# SparkFun_Roshamglo.net
KiCad netlist of a schematic drawn in EAGLE
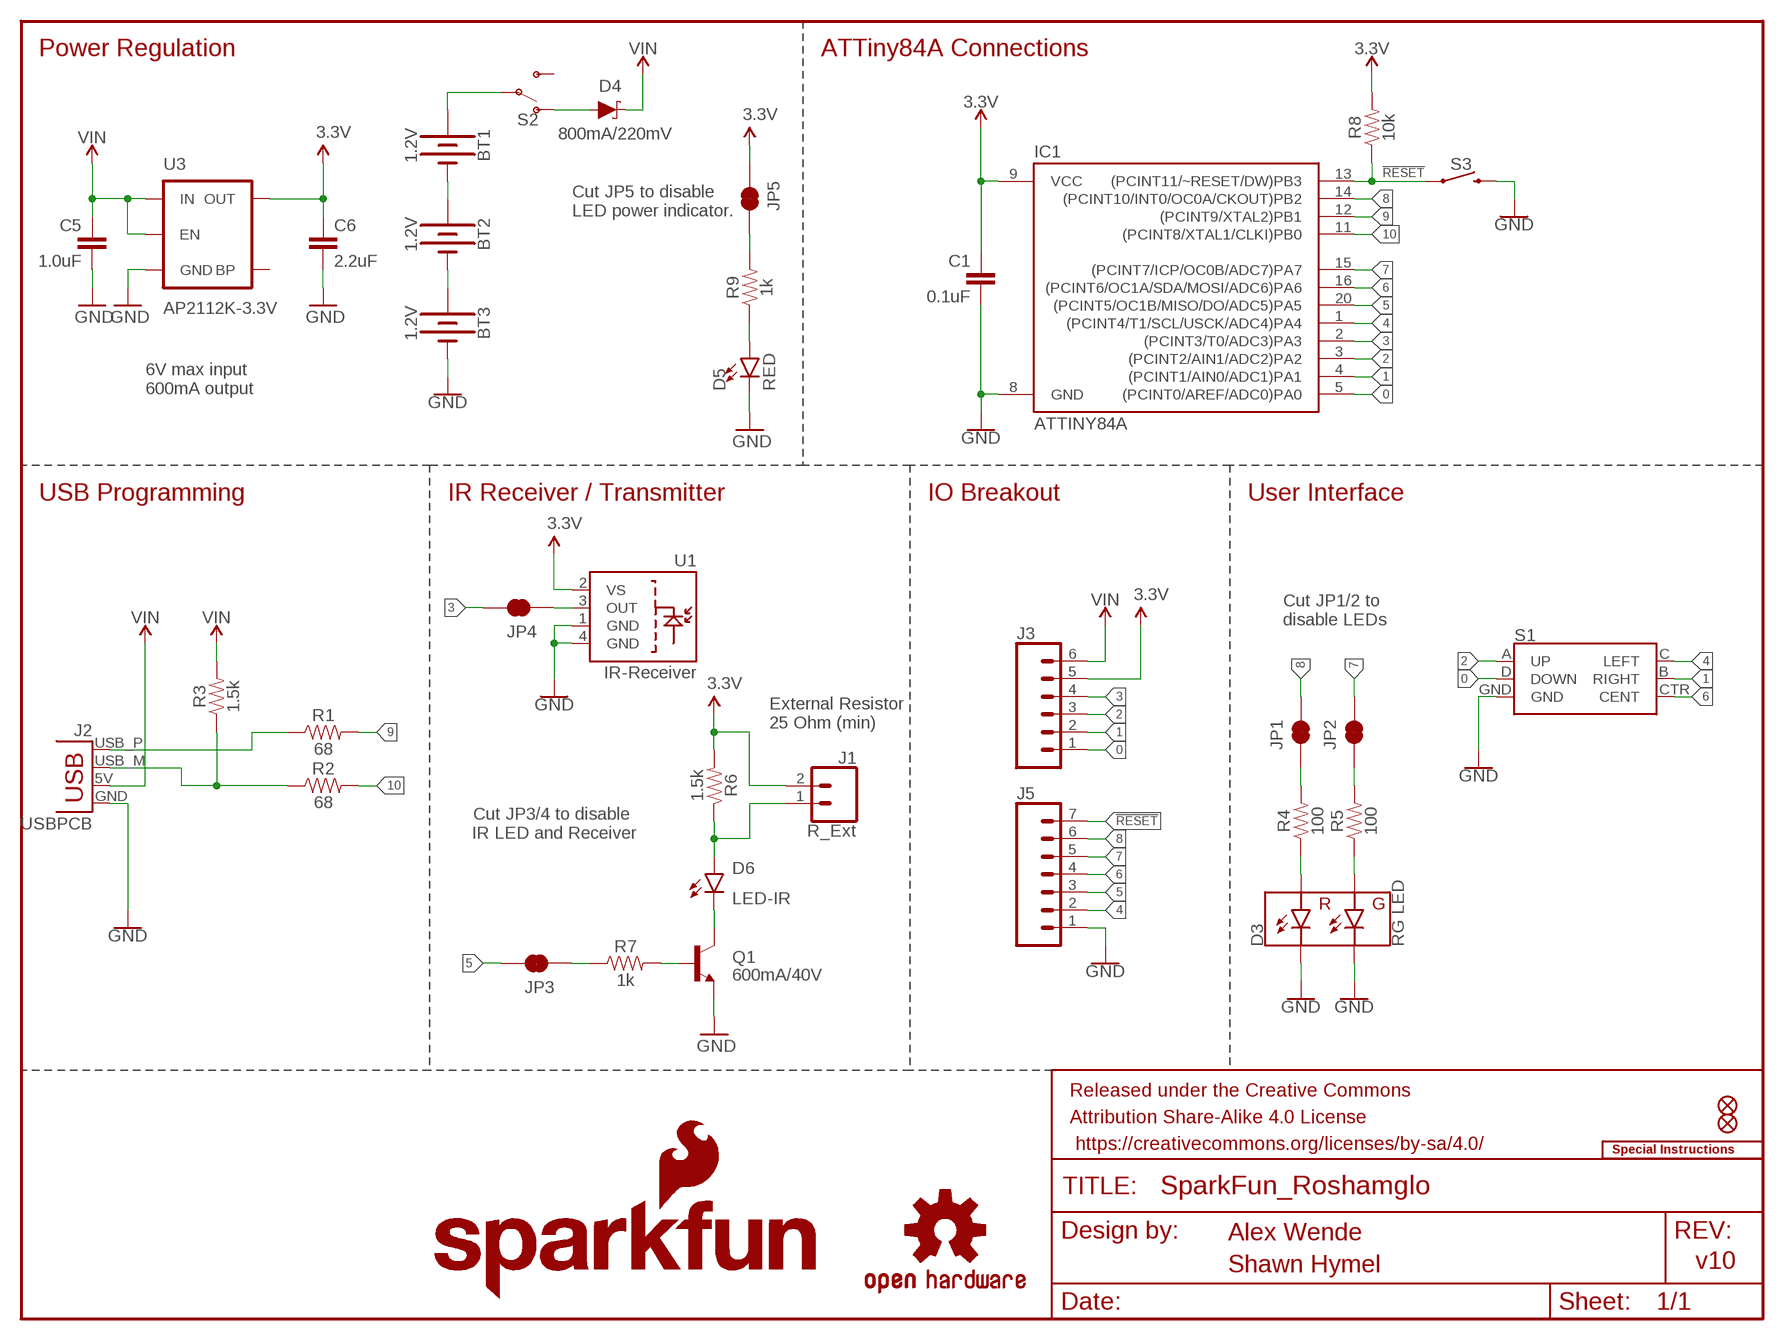
[diagram p0: schematic, sheet 1]

(export (version "E")
  (design (tool "Eeschema 10.0.6"))
  (components
    (comp (ref "BT1")
      (value "1.2V")
      (footprint "eagle-import:BATTERY-AAA-KIT")
      (libsource (lib "eagle-import") (part "BATTERY-AAA_KIT"))
    )
    (comp (ref "BT2")
      (value "1.2V")
      (footprint "eagle-import:BATTERY-AAA-KIT")
      (libsource (lib "eagle-import") (part "BATTERY-AAA_KIT"))
    )
    (comp (ref "BT3")
      (value "1.2V")
      (footprint "eagle-import:BATTERY-AAA-KIT")
      (libsource (lib "eagle-import") (part "BATTERY-AAA_KIT"))
    )
    (comp (ref "C1")
      (value "0.1uF")
      (footprint "eagle-import:0603")
      (libsource (lib "eagle-import") (part "0.1UF-0603-25V-(+80/-20%)"))
    )
    (comp (ref "C5")
      (value "1.0uF")
      (footprint "eagle-import:0805-CAP")
      (libsource (lib "eagle-import") (part "1.0UF-25V-+80/-20(0805){dblquote}"))
    )
    (comp (ref "C6")
      (value "2.2uF")
      (footprint "eagle-import:0603-CAP")
      (libsource (lib "eagle-import") (part "2.2UF-10V-20%(0603)"))
    )
    (comp (ref "D3")
      (value "RG LED")
      (footprint "eagle-import:LTST-C195KGJRKT")
      (libsource (lib "eagle-import") (part "LED-RGLTST-C195KGJRKT"))
    )
    (comp (ref "D4")
      (value "800mA/220mV")
      (footprint "eagle-import:SOD-323")
      (libsource (lib "eagle-import") (part "CUS08F30SOD-323"))
    )
    (comp (ref "D5")
      (value "RED")
      (footprint "eagle-import:LED-0603")
      (libsource (lib "eagle-import") (part "LED-RED0603"))
    )
    (comp (ref "D6")
      (value "LED-IR")
      (footprint "eagle-import:SFH4045N")
      (libsource (lib "eagle-import") (part "LED-IR-SMDSFH4045N"))
    )
    (comp (ref "FD1")
      (value "FIDUCIALUFIDUCIAL")
      (footprint "eagle-import:FIDUCIAL-MICRO")
      (libsource (lib "eagle-import") (part "FIDUCIALUFIDUCIAL"))
    )
    (comp (ref "FD2")
      (value "FIDUCIALUFIDUCIAL")
      (footprint "eagle-import:FIDUCIAL-MICRO")
      (libsource (lib "eagle-import") (part "FIDUCIALUFIDUCIAL"))
    )
    (comp (ref "FRAME1")
      (value "FRAME-LETTER")
      (footprint "eagle-import:CREATIVE_COMMONS")
      (libsource (lib "eagle-import") (part "FRAME-LETTER"))
    )
    (comp (ref "IC1")
      (value "ATTINY84A")
      (footprint "eagle-import:QFN20")
      (libsource (lib "eagle-import") (part "ATTINY84ATTINY84-20MU"))
    )
    (comp (ref "J1")
      (value "R_Ext")
      (footprint "eagle-import:1X02_NO_SILK")
      (libsource (lib "eagle-import") (part "CONN_021X02_NO_SILK"))
    )
    (comp (ref "J2")
      (value "USBPCB")
      (footprint "eagle-import:USB-A-PCB-NOPASTE")
      (libsource (lib "eagle-import") (part "USBPCB_NOPASTE"))
    )
    (comp (ref "J3")
      (value "CONN_06NO_SILK_FEMALE_PTH")
      (footprint "eagle-import:1X06_NO_SILK")
      (libsource (lib "eagle-import") (part "CONN_06NO_SILK_FEMALE_PTH"))
    )
    (comp (ref "J5")
      (value "CONN_07NO_SILK")
      (footprint "eagle-import:1X07_NO_SILK")
      (libsource (lib "eagle-import") (part "CONN_07NO_SILK"))
    )
    (comp (ref "JP1")
      (value "JUMPER-SMT_2_NC_TRACE_SILK")
      (footprint "eagle-import:SMT-JUMPER_2_NC_TRACE_SILK")
      (libsource (lib "eagle-import") (part "JUMPER-SMT_2_NC_TRACE_SILK"))
    )
    (comp (ref "JP2")
      (value "JUMPER-SMT_2_NC_TRACE_SILK")
      (footprint "eagle-import:SMT-JUMPER_2_NC_TRACE_SILK")
      (libsource (lib "eagle-import") (part "JUMPER-SMT_2_NC_TRACE_SILK"))
    )
    (comp (ref "JP3")
      (value "JUMPER-SMT_2_NC_TRACE_SILK")
      (footprint "eagle-import:SMT-JUMPER_2_NC_TRACE_SILK")
      (libsource (lib "eagle-import") (part "JUMPER-SMT_2_NC_TRACE_SILK"))
    )
    (comp (ref "JP4")
      (value "JUMPER-SMT_2_NC_TRACE_SILK")
      (footprint "eagle-import:SMT-JUMPER_2_NC_TRACE_SILK")
      (libsource (lib "eagle-import") (part "JUMPER-SMT_2_NC_TRACE_SILK"))
    )
    (comp (ref "JP5")
      (value "JUMPER-SMT_2_NC_TRACE_SILK")
      (footprint "eagle-import:SMT-JUMPER_2_NC_TRACE_SILK")
      (libsource (lib "eagle-import") (part "JUMPER-SMT_2_NC_TRACE_SILK"))
    )
    (comp (ref "LOGO1")
      (value "OSHW-LOGOS")
      (footprint "eagle-import:OSHW-LOGO-S")
      (libsource (lib "eagle-import") (part "OSHW-LOGOS"))
    )
    (comp (ref "LOGO2")
      (value "SFE_LOGO_NAME_FLAME.2_INCH")
      (footprint "eagle-import:SFE_LOGO_NAME_FLAME_.2")
      (libsource (lib "eagle-import") (part "SFE_LOGO_NAME_FLAME.2_INCH"))
    )
    (comp (ref "Q1")
      (value "600mA/40V")
      (footprint "eagle-import:SOT23-3")
      (libsource (lib "eagle-import") (part "TRANS_NPN-MMBT2222AL"))
    )
    (comp (ref "R1")
      (value "68")
      (footprint "eagle-import:0603")
      (libsource (lib "eagle-import") (part "68OHM-0603-1/10W-1%"))
    )
    (comp (ref "R2")
      (value "68")
      (footprint "eagle-import:0603")
      (libsource (lib "eagle-import") (part "68OHM-0603-1/10W-1%"))
    )
    (comp (ref "R3")
      (value "1.5k")
      (footprint "eagle-import:0603")
      (libsource (lib "eagle-import") (part "1.5KOHM-0603-1/10W-1%"))
    )
    (comp (ref "R4")
      (value "100")
      (footprint "eagle-import:0603")
      (libsource (lib "eagle-import") (part "100OHM-0603-1/10W-1%"))
    )
    (comp (ref "R5")
      (value "100")
      (footprint "eagle-import:0603")
      (libsource (lib "eagle-import") (part "100OHM-0603-1/10W-1%"))
    )
    (comp (ref "R6")
      (value "1.5k")
      (footprint "eagle-import:0603")
      (libsource (lib "eagle-import") (part "1.5KOHM-0603-1/10W-1%"))
    )
    (comp (ref "R7")
      (value "1k")
      (footprint "eagle-import:0603")
      (libsource (lib "eagle-import") (part "1KOHM-0603-1/10W-1%"))
    )
    (comp (ref "R8")
      (value "10k")
      (footprint "eagle-import:0603")
      (libsource (lib "eagle-import") (part "10KOHM-0603-1/10W-1%"))
    )
    (comp (ref "R9")
      (value "1k")
      (footprint "eagle-import:0603")
      (libsource (lib "eagle-import") (part "1KOHM-0603-1/10W-1%"))
    )
    (comp (ref "S1")
      (value "JOYSTICK_MINI")
      (footprint "eagle-import:JOYSTICK_MINI")
      (libsource (lib "eagle-import") (part "JOYSTICK_MINI"))
    )
    (comp (ref "S2")
      (value "SWITCH-SPDT-SMD-RIGHT-ANGLE")
      (footprint "eagle-import:SWITCH_SPST_SMD_A")
      (libsource (lib "eagle-import") (part "SWITCH-SPDT-SMD-RIGHT-ANGLE"))
    )
    (comp (ref "S3")
      (value "MOMENTARY-SWITCH-SPST-SMD-4.6X2.8MM")
      (footprint "eagle-import:TACTILE_SWITCH_SMD_4.6X2.8MM")
      (libsource (lib "eagle-import") (part "MOMENTARY-SWITCH-SPST-SMD-4.6X2.8MM"))
    )
    (comp (ref "U$5")
      (value "SPECIAL_INSTRUCTIONS-ORDERING")
      (footprint "eagle-import:ORDERING_INSTRUCTIONS")
      (libsource (lib "eagle-import") (part "SPECIAL_INSTRUCTIONS-ORDERING"))
    )
    (comp (ref "U1")
      (value "IR-Receiver")
      (footprint "eagle-import:TSOP75XXXWTR")
      (libsource (lib "eagle-import") (part "TSOP75XXXWSIDE_VIEW"))
    )
    (comp (ref "U3")
      (value "AP2112K-3.3V")
      (footprint "eagle-import:SOT23-5")
      (libsource (lib "eagle-import") (part "V_REG_LDOSMD"))
    )
  )
  (nets
    (net (code "1") (name "/~{RESET}") (class "Default")
      (node (ref "IC1") (pin "13") (pinfunction "(PCINT11/~{RESET/DW})PB3_13") (pintype "bidirectional"))
      (node (ref "J5") (pin "7") (pinfunction "7_7") (pintype "passive"))
      (node (ref "R8") (pin "1") (pinfunction "1_1") (pintype "passive"))
      (node (ref "S3") (pin "1") (pinfunction "1_1") (pintype "passive"))
      (node (ref "S3") (pin "2") (pinfunction "1_2") (pintype "passive"))
    )
    (net (code "2") (name "0") (class "Default")
      (node (ref "IC1") (pin "5") (pinfunction "(PCINT0/AREF/ADC0)PA0_5") (pintype "bidirectional"))
      (node (ref "J3") (pin "1") (pinfunction "1_1") (pintype "passive"))
      (node (ref "S1") (pin "D") (pinfunction "DOWN_D") (pintype "bidirectional"))
    )
    (net (code "3") (name "1") (class "Default")
      (node (ref "IC1") (pin "4") (pinfunction "(PCINT1/AIN0/ADC1)PA1_4") (pintype "bidirectional"))
      (node (ref "J3") (pin "2") (pinfunction "2_2") (pintype "passive"))
      (node (ref "S1") (pin "B") (pinfunction "RIGHT_B") (pintype "bidirectional"))
    )
    (net (code "4") (name "2") (class "Default")
      (node (ref "IC1") (pin "3") (pinfunction "(PCINT2/AIN1/ADC2)PA2_3") (pintype "bidirectional"))
      (node (ref "J3") (pin "3") (pinfunction "3_3") (pintype "passive"))
      (node (ref "S1") (pin "A") (pinfunction "UP_A") (pintype "bidirectional"))
    )
    (net (code "5") (name "3") (class "Default")
      (node (ref "IC1") (pin "2") (pinfunction "(PCINT3/T0/ADC3)PA3_2") (pintype "bidirectional"))
      (node (ref "J3") (pin "4") (pinfunction "4_4") (pintype "passive"))
      (node (ref "JP4") (pin "2") (pinfunction "2_2") (pintype "passive"))
    )
    (net (code "6") (name "3.3V") (class "Default")
      (node (ref "C1") (pin "1") (pinfunction "1_1") (pintype "passive"))
      (node (ref "C6") (pin "1") (pinfunction "1_1") (pintype "passive"))
      (node (ref "IC1") (pin "9") (pinfunction "VCC_9") (pintype "bidirectional"))
      (node (ref "J1") (pin "2") (pinfunction "2_2") (pintype "passive"))
      (node (ref "J3") (pin "5") (pinfunction "5_5") (pintype "passive"))
      (node (ref "JP5") (pin "1") (pinfunction "1_1") (pintype "passive"))
      (node (ref "R6") (pin "2") (pinfunction "2_2") (pintype "passive"))
      (node (ref "R8") (pin "2") (pinfunction "2_2") (pintype "passive"))
      (node (ref "U1") (pin "2") (pinfunction "VS_2") (pintype "bidirectional"))
      (node (ref "U3") (pin "5") (pinfunction "OUT_5") (pintype "passive"))
    )
    (net (code "7") (name "4") (class "Default")
      (node (ref "IC1") (pin "1") (pinfunction "(PCINT4/T1/SCL/USCK/ADC4)PA4_1") (pintype "bidirectional"))
      (node (ref "J5") (pin "2") (pinfunction "2_2") (pintype "passive"))
      (node (ref "S1") (pin "C") (pinfunction "LEFT_C") (pintype "bidirectional"))
    )
    (net (code "8") (name "5") (class "Default")
      (node (ref "IC1") (pin "20") (pinfunction "(PCINT5/OC1B/MISO/DO/ADC5)PA5_20") (pintype "bidirectional"))
      (node (ref "J5") (pin "3") (pinfunction "3_3") (pintype "passive"))
      (node (ref "JP3") (pin "2") (pinfunction "2_2") (pintype "passive"))
    )
    (net (code "9") (name "6") (class "Default")
      (node (ref "IC1") (pin "16") (pinfunction "(PCINT6/OC1A/SDA/MOSI/ADC6)PA6_16") (pintype "bidirectional"))
      (node (ref "J5") (pin "4") (pinfunction "4_4") (pintype "passive"))
      (node (ref "S1") (pin "CTR") (pinfunction "CENT_CTR") (pintype "bidirectional"))
    )
    (net (code "10") (name "7") (class "Default")
      (node (ref "IC1") (pin "15") (pinfunction "(PCINT7/ICP/OC0B/ADC7)PA7_15") (pintype "bidirectional"))
      (node (ref "J5") (pin "5") (pinfunction "5_5") (pintype "passive"))
      (node (ref "JP2") (pin "2") (pinfunction "2_2") (pintype "passive"))
    )
    (net (code "11") (name "8") (class "Default")
      (node (ref "IC1") (pin "14") (pinfunction "(PCINT10/INT0/OC0A/CKOUT)PB2_14") (pintype "bidirectional"))
      (node (ref "J5") (pin "6") (pinfunction "6_6") (pintype "passive"))
      (node (ref "JP1") (pin "2") (pinfunction "2_2") (pintype "passive"))
    )
    (net (code "12") (name "9") (class "Default")
      (node (ref "IC1") (pin "12") (pinfunction "(PCINT9/XTAL2)PB1_12") (pintype "bidirectional"))
      (node (ref "R1") (pin "2") (pinfunction "2_2") (pintype "passive"))
    )
    (net (code "13") (name "10") (class "Default")
      (node (ref "IC1") (pin "11") (pinfunction "(PCINT8/XTAL1/CLKI)PB0_11") (pintype "bidirectional"))
      (node (ref "R2") (pin "2") (pinfunction "2_2") (pintype "passive"))
    )
    (net (code "14") (name "GND") (class "Default")
      (node (ref "BT3") (pin "GND@1") (pinfunction "-_GND@1") (pintype "power_in"))
      (node (ref "C1") (pin "2") (pinfunction "2_2") (pintype "passive"))
      (node (ref "C5") (pin "2") (pinfunction "2_2") (pintype "passive"))
      (node (ref "C6") (pin "2") (pinfunction "2_2") (pintype "passive"))
      (node (ref "D3") (pin "P$3") (pinfunction "GC_P$3") (pintype "passive"))
      (node (ref "D3") (pin "P$4") (pinfunction "RC_P$4") (pintype "passive"))
      (node (ref "D5") (pin "C") (pinfunction "C_C") (pintype "passive"))
      (node (ref "IC1") (pin "8") (pinfunction "GND_8") (pintype "bidirectional"))
      (node (ref "J2") (pin "GND") (pinfunction "GND_GND") (pintype "bidirectional"))
      (node (ref "J5") (pin "1") (pinfunction "1_1") (pintype "passive"))
      (node (ref "Q1") (pin "2") (pinfunction "E_2") (pintype "passive"))
      (node (ref "S1") (pin "GND") (pinfunction "GND_GND") (pintype "bidirectional"))
      (node (ref "S3") (pin "3") (pinfunction "2_3") (pintype "passive"))
      (node (ref "S3") (pin "4") (pinfunction "2_4") (pintype "passive"))
      (node (ref "U1") (pin "1") (pinfunction "GND_1") (pintype "bidirectional"))
      (node (ref "U1") (pin "4") (pinfunction "GND_4") (pintype "bidirectional"))
      (node (ref "U3") (pin "2") (pinfunction "GND_2") (pintype "input"))
    )
    (net (code "15") (name "Net-(BT1-+)") (class "Default")
      (node (ref "BT1") (pin "PWR@1") (pinfunction "+_PWR@1") (pintype "power_in"))
      (node (ref "S2") (pin "2") (pinfunction "P_2") (pintype "passive"))
    )
    (net (code "16") (name "Net-(BT1--)") (class "Default")
      (node (ref "BT1") (pin "GND@1") (pinfunction "-_GND@1") (pintype "power_in"))
      (node (ref "BT2") (pin "PWR@1") (pinfunction "+_PWR@1") (pintype "power_in"))
    )
    (net (code "17") (name "Net-(BT2--)") (class "Default")
      (node (ref "BT2") (pin "GND@1") (pinfunction "-_GND@1") (pintype "power_in"))
      (node (ref "BT3") (pin "PWR@1") (pinfunction "+_PWR@1") (pintype "power_in"))
    )
    (net (code "18") (name "Net-(D3-GA)") (class "Default")
      (node (ref "D3") (pin "P$1") (pinfunction "GA_P$1") (pintype "passive"))
      (node (ref "R5") (pin "1") (pinfunction "1_1") (pintype "passive"))
    )
    (net (code "19") (name "Net-(D3-RA)") (class "Default")
      (node (ref "D3") (pin "P$2") (pinfunction "RA_P$2") (pintype "passive"))
      (node (ref "R4") (pin "1") (pinfunction "1_1") (pintype "passive"))
    )
    (net (code "20") (name "Net-(D5-PadA)") (class "Default")
      (node (ref "D5") (pin "A") (pinfunction "A_A") (pintype "passive"))
      (node (ref "R9") (pin "1") (pinfunction "1_1") (pintype "passive"))
    )
    (net (code "21") (name "Net-(D6-A)") (class "Default")
      (node (ref "D6") (pin "2") (pinfunction "A_2") (pintype "passive"))
      (node (ref "J1") (pin "1") (pinfunction "1_1") (pintype "passive"))
      (node (ref "R6") (pin "1") (pinfunction "1_1") (pintype "passive"))
    )
    (net (code "22") (name "Net-(D6-C)") (class "Default")
      (node (ref "D6") (pin "1") (pinfunction "C_1") (pintype "passive"))
      (node (ref "Q1") (pin "3") (pinfunction "C_3") (pintype "passive"))
    )
    (net (code "23") (name "Net-(J2-D+)") (class "Default")
      (node (ref "J2") (pin "USB_P") (pinfunction "D+_USB_P") (pintype "bidirectional"))
      (node (ref "R1") (pin "1") (pinfunction "1_1") (pintype "passive"))
    )
    (net (code "24") (name "Net-(J2-D-)") (class "Default")
      (node (ref "J2") (pin "USB_M") (pinfunction "D-_USB_M") (pintype "bidirectional"))
      (node (ref "R2") (pin "1") (pinfunction "1_1") (pintype "passive"))
      (node (ref "R3") (pin "1") (pinfunction "1_1") (pintype "passive"))
    )
    (net (code "25") (name "Net-(JP1-Pad1)") (class "Default")
      (node (ref "JP1") (pin "1") (pinfunction "1_1") (pintype "passive"))
      (node (ref "R4") (pin "2") (pinfunction "2_2") (pintype "passive"))
    )
    (net (code "26") (name "Net-(JP2-Pad1)") (class "Default")
      (node (ref "JP2") (pin "1") (pinfunction "1_1") (pintype "passive"))
      (node (ref "R5") (pin "2") (pinfunction "2_2") (pintype "passive"))
    )
    (net (code "27") (name "Net-(JP3-Pad1)") (class "Default")
      (node (ref "JP3") (pin "1") (pinfunction "1_1") (pintype "passive"))
      (node (ref "R7") (pin "1") (pinfunction "1_1") (pintype "passive"))
    )
    (net (code "28") (name "Net-(JP5-Pad2)") (class "Default")
      (node (ref "JP5") (pin "2") (pinfunction "2_2") (pintype "passive"))
      (node (ref "R9") (pin "2") (pinfunction "2_2") (pintype "passive"))
    )
    (net (code "29") (name "Net-(Q1-B)") (class "Default")
      (node (ref "Q1") (pin "1") (pinfunction "B_1") (pintype "passive"))
      (node (ref "R7") (pin "2") (pinfunction "2_2") (pintype "passive"))
    )
    (net (code "30") (name "Net-(S2-O)") (class "Default")
      (node (ref "D4") (pin "A") (pinfunction "A_A") (pintype "passive"))
      (node (ref "S2") (pin "1") (pinfunction "O_1") (pintype "passive"))
    )
    (net (code "31") (name "Net-(U1-OUT)") (class "Default")
      (node (ref "JP4") (pin "1") (pinfunction "1_1") (pintype "passive"))
      (node (ref "U1") (pin "3") (pinfunction "OUT_3") (pintype "bidirectional"))
    )
    (net (code "32") (name "VIN") (class "Default")
      (node (ref "C5") (pin "1") (pinfunction "1_1") (pintype "passive"))
      (node (ref "D4") (pin "C") (pinfunction "C_C") (pintype "passive"))
      (node (ref "J2") (pin "5V") (pinfunction "VBUS_5V") (pintype "bidirectional"))
      (node (ref "J3") (pin "6") (pinfunction "6_6") (pintype "passive"))
      (node (ref "R3") (pin "2") (pinfunction "2_2") (pintype "passive"))
      (node (ref "U3") (pin "1") (pinfunction "IN_1") (pintype "input"))
      (node (ref "U3") (pin "3") (pinfunction "EN_3") (pintype "input"))
    )
    (net (code "33") (name "unconnected-(S2-S-Pad3)") (class "Default")
      (node (ref "S2") (pin "3") (pinfunction "S_3") (pintype "passive"))
    )
    (net (code "34") (name "unconnected-(U3-BP-Pad4)") (class "Default")
      (node (ref "U3") (pin "4") (pinfunction "BP_4") (pintype "input"))
    )
  )
)
